# P05_Power_Supply2.net
KiCad netlist of a schematic drawn in Altium Designer
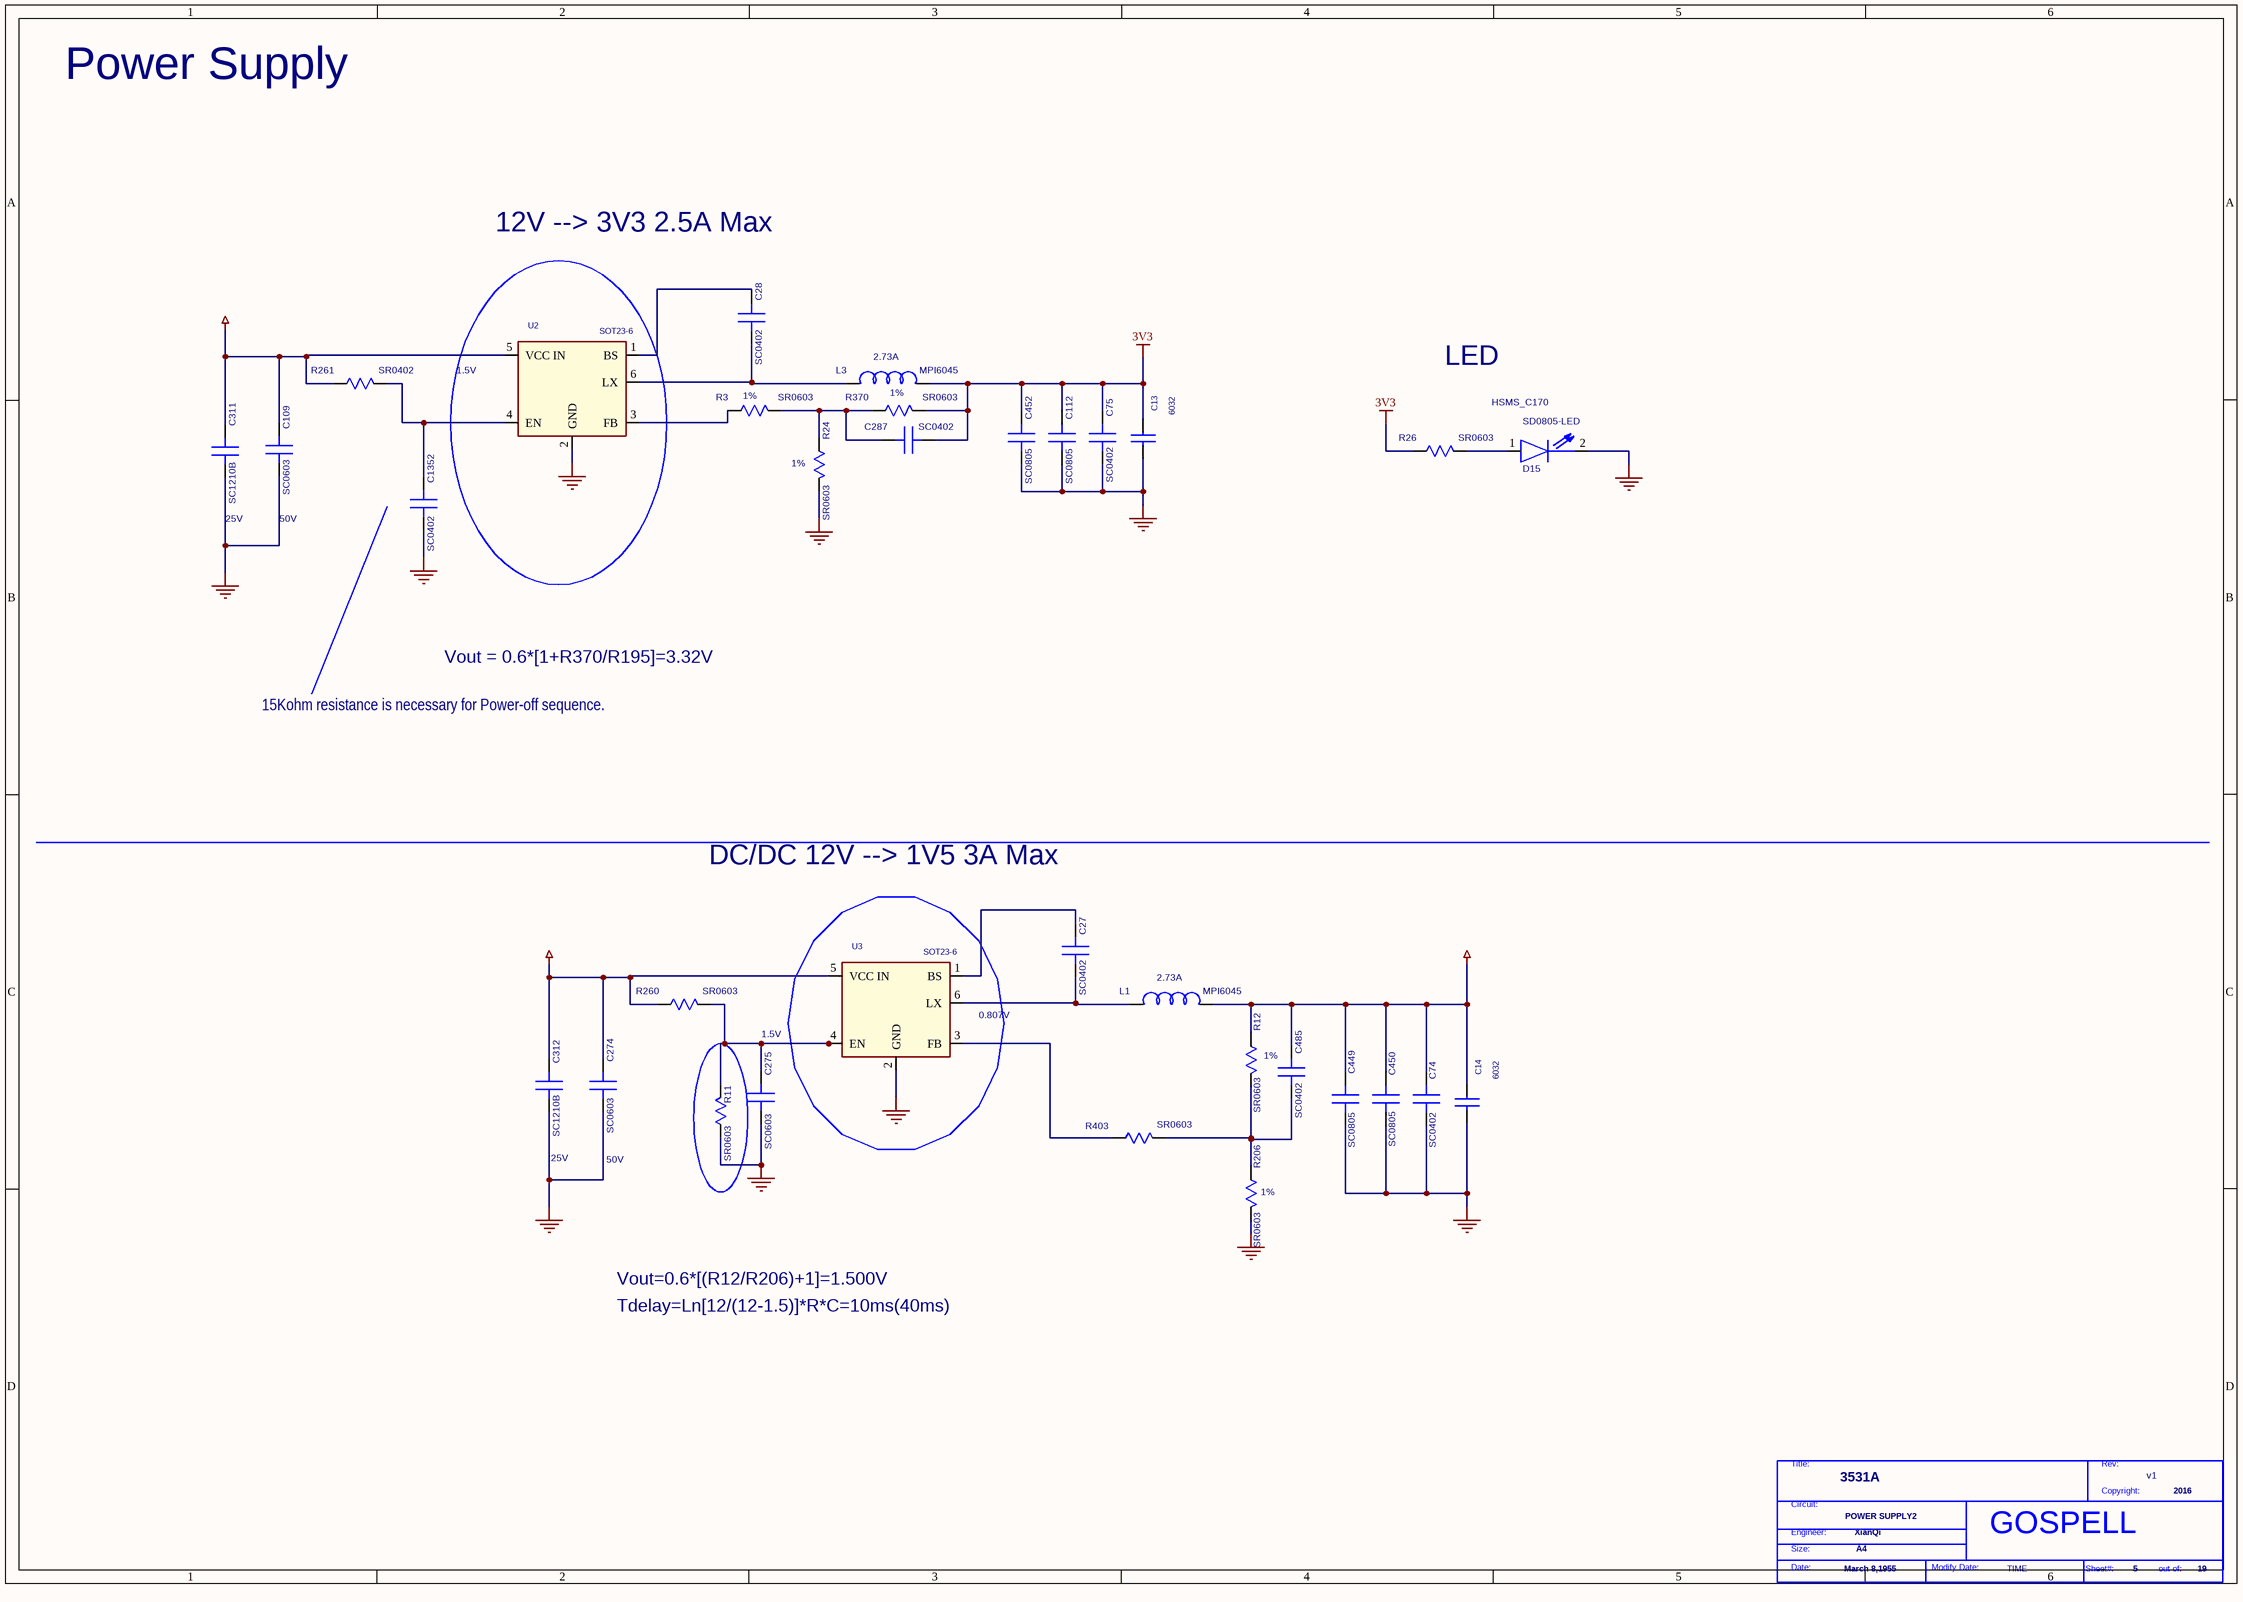
[diagram p0: P05 Power Supply2.SchDoc]

(export (version "E")
  (design (tool "Eeschema 10.0.6"))
  (components
    (comp (ref "C13") (value "6032") (footprint "6032") (libsource (lib "*") (part "CAP NP")))
    (comp (ref "C14") (value "6032") (footprint "6032") (libsource (lib "*") (part "CAP NP")))
    (comp (ref "C27") (value "SC0402") (libsource (lib "*") (part "C_0_Dup2")))
    (comp (ref "C28") (value "SC0402") (libsource (lib "*") (part "C_0_Dup2")))
    (comp (ref "C74") (value "SC0402") (libsource (lib "*") (part "C_0_Dup2")))
    (comp (ref "C75") (value "SC0402") (libsource (lib "*") (part "C_0_Dup2")))
    (comp (ref "C109") (value "SC0603") (libsource (lib "*") (part "C_0_Dup2")))
    (comp (ref "C112") (value "SC0805") (libsource (lib "*") (part "C_0_Dup2")))
    (comp (ref "C274") (value "SC0603") (libsource (lib "*") (part "C_0_Dup2")))
    (comp (ref "C275") (value "SC0603") (libsource (lib "*") (part "C_0_Dup2")))
    (comp (ref "C287") (value "SC0402") (libsource (lib "*") (part "C_0_Dup2")))
    (comp (ref "C311") (value "SC1210B") (libsource (lib "*") (part "C_0_Dup2")))
    (comp (ref "C312") (value "SC1210B") (libsource (lib "*") (part "C_0_Dup2")))
    (comp (ref "C449") (value "SC0805") (libsource (lib "*") (part "C_0_Dup2")))
    (comp (ref "C450") (value "SC0805") (libsource (lib "*") (part "C_0_Dup2")))
    (comp (ref "C452") (value "SC0805") (libsource (lib "*") (part "C_0_Dup2")))
    (comp (ref "C485") (value "SC0402") (libsource (lib "*") (part "C_0_Dup2")))
    (comp (ref "C1352") (value "SC0402") (libsource (lib "*") (part "C_0_Dup2")))
    (comp (ref "D15")
      (value "SD0805-LED")
      (fields (field (name "DEVICE") "HSMS_C170"))
      (libsource (lib "*") (part "LED_1"))
    )
    (comp (ref "L1") (value "MPI6045") (libsource (lib "*") (part "L_0_Dup1")))
    (comp (ref "L3") (value "MPI6045") (libsource (lib "*") (part "L_0_Dup1")))
    (comp (ref "R3") (value "SR0603") (libsource (lib "*") (part "R_1")))
    (comp (ref "R11") (value "SR0603") (libsource (lib "*") (part "R_1")))
    (comp (ref "R12") (value "SR0603") (libsource (lib "*") (part "R_1")))
    (comp (ref "R24") (value "SR0603") (libsource (lib "*") (part "R_1")))
    (comp (ref "R26") (value "SR0603") (libsource (lib "*") (part "R_1")))
    (comp (ref "R206") (value "SR0603") (libsource (lib "*") (part "R_1")))
    (comp (ref "R260") (value "SR0603") (libsource (lib "*") (part "R_1")))
    (comp (ref "R261") (value "SR0402") (libsource (lib "*") (part "R_1")))
    (comp (ref "R370") (value "SR0603") (libsource (lib "*") (part "R_1")))
    (comp (ref "R403") (value "SR0603") (libsource (lib "*") (part "R_1")))
    (comp (ref "U2") (value "SOT23-6") (footprint "SOT23-6") (libsource (lib "*") (part "SY8120")))
    (comp (ref "U3") (value "SOT23-6") (footprint "SOT23-6") (libsource (lib "*") (part "SY8120")))
  )
  (nets
    (net (code "1") (name "1V5") (class "Default")
      (node (ref "C14") (pin "1") (pinfunction "1_1") (pintype "passive"))
      (node (ref "C449") (pin "1") (pinfunction "A_1") (pintype "passive"))
      (node (ref "C450") (pin "1") (pinfunction "A_1") (pintype "passive"))
      (node (ref "C485") (pin "1") (pinfunction "A_1") (pintype "passive"))
      (node (ref "C74") (pin "1") (pinfunction "A_1") (pintype "passive"))
      (node (ref "L1") (pin "2") (pinfunction "B_2") (pintype "passive"))
      (node (ref "R12") (pin "1") (pinfunction "A_1") (pintype "passive"))
    )
    (net (code "2") (name "3V3") (class "Default")
      (node (ref "C112") (pin "1") (pinfunction "A_1") (pintype "passive"))
      (node (ref "C13") (pin "1") (pinfunction "1_1") (pintype "passive"))
      (node (ref "C287") (pin "2") (pinfunction "B_2") (pintype "passive"))
      (node (ref "C452") (pin "1") (pinfunction "A_1") (pintype "passive"))
      (node (ref "C75") (pin "1") (pinfunction "A_1") (pintype "passive"))
      (node (ref "L3") (pin "2") (pinfunction "B_2") (pintype "passive"))
      (node (ref "R26") (pin "1") (pinfunction "A_1") (pintype "passive"))
      (node (ref "R370") (pin "2") (pinfunction "B_2") (pintype "passive"))
    )
    (net (code "3") (name "12V0") (class "Default")
      (node (ref "C109") (pin "1") (pinfunction "A_1") (pintype "passive"))
      (node (ref "C274") (pin "1") (pinfunction "A_1") (pintype "passive"))
      (node (ref "C311") (pin "1") (pinfunction "A_1") (pintype "passive"))
      (node (ref "C312") (pin "1") (pinfunction "A_1") (pintype "passive"))
      (node (ref "R260") (pin "1") (pinfunction "A_1") (pintype "passive"))
      (node (ref "R261") (pin "1") (pinfunction "A_1") (pintype "passive"))
      (node (ref "U2") (pin "5") (pinfunction "VCC_IN_5") (pintype "passive"))
      (node (ref "U3") (pin "5") (pinfunction "VCC_IN_5") (pintype "passive"))
    )
    (net (code "4") (name "GND") (class "Default")
      (node (ref "C109") (pin "2") (pinfunction "B_2") (pintype "passive"))
      (node (ref "C112") (pin "2") (pinfunction "B_2") (pintype "passive"))
      (node (ref "C13") (pin "2") (pinfunction "2_2") (pintype "passive"))
      (node (ref "C1352") (pin "2") (pinfunction "B_2") (pintype "passive"))
      (node (ref "C14") (pin "2") (pinfunction "2_2") (pintype "passive"))
      (node (ref "C274") (pin "2") (pinfunction "B_2") (pintype "passive"))
      (node (ref "C275") (pin "2") (pinfunction "B_2") (pintype "passive"))
      (node (ref "C311") (pin "2") (pinfunction "B_2") (pintype "passive"))
      (node (ref "C312") (pin "2") (pinfunction "B_2") (pintype "passive"))
      (node (ref "C449") (pin "2") (pinfunction "B_2") (pintype "passive"))
      (node (ref "C450") (pin "2") (pinfunction "B_2") (pintype "passive"))
      (node (ref "C452") (pin "2") (pinfunction "B_2") (pintype "passive"))
      (node (ref "C74") (pin "2") (pinfunction "B_2") (pintype "passive"))
      (node (ref "C75") (pin "2") (pinfunction "B_2") (pintype "passive"))
      (node (ref "D15") (pin "2") (pinfunction "B_2") (pintype "passive"))
      (node (ref "R11") (pin "1") (pinfunction "A_1") (pintype "passive"))
      (node (ref "R206") (pin "2") (pinfunction "B_2") (pintype "passive"))
      (node (ref "R24") (pin "2") (pinfunction "B_2") (pintype "passive"))
      (node (ref "U2") (pin "2") (pinfunction "GND_2") (pintype "passive"))
      (node (ref "U3") (pin "2") (pinfunction "GND_2") (pintype "passive"))
    )
    (net (code "5") (name "Net-(C27-A)") (class "Default")
      (node (ref "C27") (pin "1") (pinfunction "A_1") (pintype "passive"))
      (node (ref "U3") (pin "1") (pinfunction "BS_1") (pintype "passive"))
    )
    (net (code "6") (name "Net-(C27-B)") (class "Default")
      (node (ref "C27") (pin "2") (pinfunction "B_2") (pintype "passive"))
      (node (ref "L1") (pin "1") (pinfunction "A_1") (pintype "passive"))
      (node (ref "U3") (pin "6") (pinfunction "LX_6") (pintype "passive"))
    )
    (net (code "7") (name "Net-(C28-A)") (class "Default")
      (node (ref "C28") (pin "1") (pinfunction "A_1") (pintype "passive"))
      (node (ref "U2") (pin "1") (pinfunction "BS_1") (pintype "passive"))
    )
    (net (code "8") (name "Net-(C28-B)") (class "Default")
      (node (ref "C28") (pin "2") (pinfunction "B_2") (pintype "passive"))
      (node (ref "L3") (pin "1") (pinfunction "A_1") (pintype "passive"))
      (node (ref "U2") (pin "6") (pinfunction "LX_6") (pintype "passive"))
    )
    (net (code "9") (name "Net-(C275-A)") (class "Default")
      (node (ref "C275") (pin "1") (pinfunction "A_1") (pintype "passive"))
      (node (ref "R11") (pin "2") (pinfunction "B_2") (pintype "passive"))
      (node (ref "R260") (pin "2") (pinfunction "B_2") (pintype "passive"))
      (node (ref "U3") (pin "4") (pinfunction "EN_4") (pintype "passive"))
    )
    (net (code "10") (name "Net-(C287-A)") (class "Default")
      (node (ref "C287") (pin "1") (pinfunction "A_1") (pintype "passive"))
      (node (ref "R24") (pin "1") (pinfunction "A_1") (pintype "passive"))
      (node (ref "R3") (pin "2") (pinfunction "B_2") (pintype "passive"))
      (node (ref "R370") (pin "1") (pinfunction "A_1") (pintype "passive"))
    )
    (net (code "11") (name "Net-(C485-B)") (class "Default")
      (node (ref "C485") (pin "2") (pinfunction "B_2") (pintype "passive"))
      (node (ref "R12") (pin "2") (pinfunction "B_2") (pintype "passive"))
      (node (ref "R206") (pin "1") (pinfunction "A_1") (pintype "passive"))
      (node (ref "R403") (pin "2") (pinfunction "B_2") (pintype "passive"))
    )
    (net (code "12") (name "Net-(C1352-A)") (class "Default")
      (node (ref "C1352") (pin "1") (pinfunction "A_1") (pintype "passive"))
      (node (ref "R261") (pin "2") (pinfunction "B_2") (pintype "passive"))
      (node (ref "U2") (pin "4") (pinfunction "EN_4") (pintype "passive"))
    )
    (net (code "13") (name "Net-(D15-A)") (class "Default")
      (node (ref "D15") (pin "1") (pinfunction "A_1") (pintype "passive"))
      (node (ref "R26") (pin "2") (pinfunction "B_2") (pintype "passive"))
    )
    (net (code "14") (name "Net-(R3-A)") (class "Default")
      (node (ref "R3") (pin "1") (pinfunction "A_1") (pintype "passive"))
      (node (ref "U2") (pin "3") (pinfunction "FB_3") (pintype "passive"))
    )
    (net (code "15") (name "Net-(R403-A)") (class "Default")
      (node (ref "R403") (pin "1") (pinfunction "A_1") (pintype "passive"))
      (node (ref "U3") (pin "3") (pinfunction "FB_3") (pintype "passive"))
    )
  )
)
